# FabScan-Shield_v15.net
KiCad netlist of a schematic drawn in EAGLE
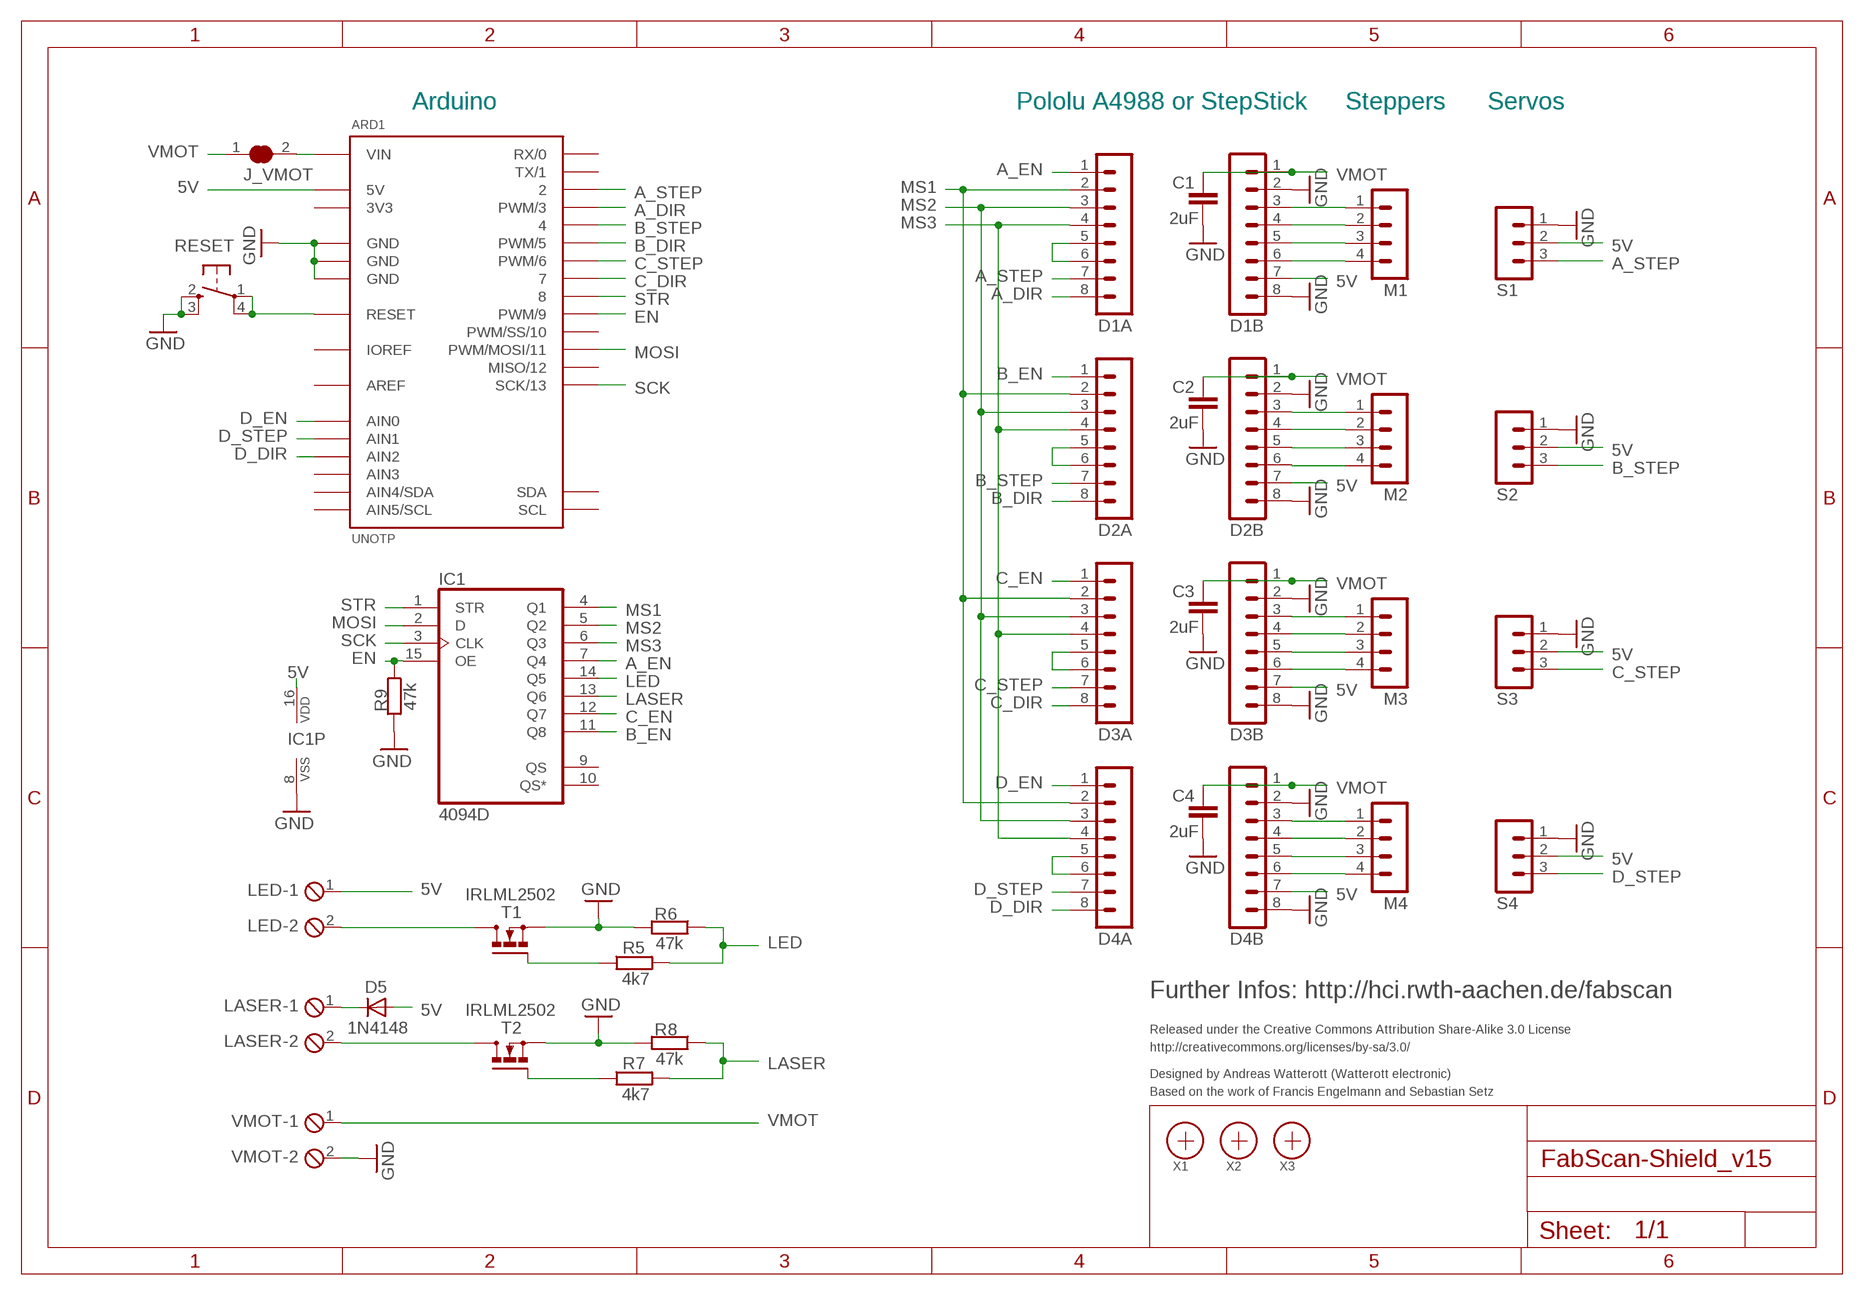
[diagram p0: schematic, sheet 1]

(export (version "E")
  (design (tool "Eeschema 10.0.6"))
  (components
    (comp (ref "ARD1")
      (value "UNOTP")
      (footprint "eagle-import:UNOTP")
      (libsource (lib "eagle-import") (part "UNOTP"))
    )
    (comp (ref "C1")
      (value "2uF")
      (footprint "eagle-import:C0603")
      (libsource (lib "eagle-import") (part "C-EUC0603"))
    )
    (comp (ref "C2")
      (value "2uF")
      (footprint "eagle-import:C0603")
      (libsource (lib "eagle-import") (part "C-EUC0603"))
    )
    (comp (ref "C3")
      (value "2uF")
      (footprint "eagle-import:C0603")
      (libsource (lib "eagle-import") (part "C-EUC0603"))
    )
    (comp (ref "C4")
      (value "2uF")
      (footprint "eagle-import:C0603")
      (libsource (lib "eagle-import") (part "C-EUC0603"))
    )
    (comp (ref "D1A")
      (value "MA08-1")
      (footprint "eagle-import:MA08-1")
      (libsource (lib "eagle-import") (part "MA08-1"))
    )
    (comp (ref "D1B")
      (value "MA08-1")
      (footprint "eagle-import:MA08-1")
      (libsource (lib "eagle-import") (part "MA08-1"))
    )
    (comp (ref "D2A")
      (value "MA08-1")
      (footprint "eagle-import:MA08-1")
      (libsource (lib "eagle-import") (part "MA08-1"))
    )
    (comp (ref "D2B")
      (value "MA08-1")
      (footprint "eagle-import:MA08-1")
      (libsource (lib "eagle-import") (part "MA08-1"))
    )
    (comp (ref "D3A")
      (value "MA08-1")
      (footprint "eagle-import:MA08-1")
      (libsource (lib "eagle-import") (part "MA08-1"))
    )
    (comp (ref "D3B")
      (value "MA08-1")
      (footprint "eagle-import:MA08-1")
      (libsource (lib "eagle-import") (part "MA08-1"))
    )
    (comp (ref "D4A")
      (value "MA08-1")
      (footprint "eagle-import:MA08-1")
      (libsource (lib "eagle-import") (part "MA08-1"))
    )
    (comp (ref "D4B")
      (value "MA08-1")
      (footprint "eagle-import:MA08-1")
      (libsource (lib "eagle-import") (part "MA08-1"))
    )
    (comp (ref "D5")
      (value "1N4148")
      (footprint "eagle-import:SOD106-R")
      (libsource (lib "eagle-import") (part "DIODE-SOD106-R"))
    )
    (comp (ref "IC1")
      (value "4094D")
      (footprint "eagle-import:SO16")
      (libsource (lib "eagle-import") (part "4094D"))
    )
    (comp (ref "J_VMOT")
      (value "SJ")
      (footprint "eagle-import:SJ")
      (libsource (lib "eagle-import") (part "SJ"))
    )
    (comp (ref "LASER")
      (value "MPT2")
      (footprint "eagle-import:2POL254")
      (fields (field (name "OC_FARNELL") "unknown") (field (name "OC_NEWARK") "unknown"))
      (libsource (lib "eagle-import") (part "MPT2"))
    )
    (comp (ref "LED")
      (value "MPT2")
      (footprint "eagle-import:2POL254")
      (libsource (lib "eagle-import") (part "MPT2"))
    )
    (comp (ref "M1")
      (value "MA04-1")
      (footprint "eagle-import:MA04-1")
      (libsource (lib "eagle-import") (part "MA04-1"))
    )
    (comp (ref "M2")
      (value "MA04-1")
      (footprint "eagle-import:MA04-1")
      (fields (field (name "OC_FARNELL") "unknown") (field (name "OC_NEWARK") "unknown"))
      (libsource (lib "eagle-import") (part "MA04-1"))
    )
    (comp (ref "M3")
      (value "MA04-1")
      (footprint "eagle-import:MA04-1")
      (fields (field (name "OC_FARNELL") "unknown") (field (name "OC_NEWARK") "unknown"))
      (libsource (lib "eagle-import") (part "MA04-1"))
    )
    (comp (ref "M4")
      (value "MA04-1")
      (footprint "eagle-import:MA04-1")
      (fields (field (name "OC_FARNELL") "unknown") (field (name "OC_NEWARK") "unknown"))
      (libsource (lib "eagle-import") (part "MA04-1"))
    )
    (comp (ref "R5")
      (value "4k7")
      (footprint "eagle-import:R0603")
      (libsource (lib "eagle-import") (part "R-EU_R0603"))
    )
    (comp (ref "R6")
      (value "47k")
      (footprint "eagle-import:R0603")
      (libsource (lib "eagle-import") (part "R-EU_R0603"))
    )
    (comp (ref "R7")
      (value "4k7")
      (footprint "eagle-import:R0603")
      (libsource (lib "eagle-import") (part "R-EU_R0603"))
    )
    (comp (ref "R8")
      (value "47k")
      (footprint "eagle-import:R0603")
      (libsource (lib "eagle-import") (part "R-EU_R0603"))
    )
    (comp (ref "R9")
      (value "47k")
      (footprint "eagle-import:R0603")
      (libsource (lib "eagle-import") (part "R-EU_R0603"))
    )
    (comp (ref "RESET")
      (value "SW_SMDS")
      (footprint "eagle-import:SW_SMD4")
      (libsource (lib "eagle-import") (part "SW_SMDS"))
    )
    (comp (ref "S1")
      (value "MA03-1")
      (footprint "eagle-import:MA03-1")
      (libsource (lib "eagle-import") (part "MA03-1"))
    )
    (comp (ref "S2")
      (value "MA03-1")
      (footprint "eagle-import:MA03-1")
      (libsource (lib "eagle-import") (part "MA03-1"))
    )
    (comp (ref "S3")
      (value "MA03-1")
      (footprint "eagle-import:MA03-1")
      (libsource (lib "eagle-import") (part "MA03-1"))
    )
    (comp (ref "S4")
      (value "MA03-1")
      (footprint "eagle-import:MA03-1")
      (libsource (lib "eagle-import") (part "MA03-1"))
    )
    (comp (ref "T1")
      (value "IRLML2502")
      (footprint "eagle-import:MICRO3")
      (libsource (lib "eagle-import") (part "IRLML2502"))
    )
    (comp (ref "T2")
      (value "IRLML2502")
      (footprint "eagle-import:MICRO3")
      (libsource (lib "eagle-import") (part "IRLML2502"))
    )
    (comp (ref "VMOT")
      (value "MPT2")
      (footprint "eagle-import:2POL254")
      (fields (field (name "OC_FARNELL") "unknown") (field (name "OC_NEWARK") "unknown"))
      (libsource (lib "eagle-import") (part "MPT2"))
    )
    (comp (ref "X1")
      (value "PASSER")
      (footprint "eagle-import:PASSER")
      (libsource (lib "eagle-import") (part "PASSER"))
    )
    (comp (ref "X2")
      (value "PASSER")
      (footprint "eagle-import:PASSER")
      (libsource (lib "eagle-import") (part "PASSER"))
    )
    (comp (ref "X3")
      (value "PASSER")
      (footprint "eagle-import:PASSER")
      (libsource (lib "eagle-import") (part "PASSER"))
    )
  )
  (nets
    (net (code "1") (name "/3V3") (class "Default")
      (node (ref "ARD1") (pin "3V3") (pinfunction "3V3_3V3") (pintype "power_in"))
    )
    (net (code "2") (name "/5V") (class "Default")
      (node (ref "ARD1") (pin "5V") (pinfunction "5V_5V") (pintype "power_in"))
      (node (ref "D1B") (pin "7") (pinfunction "7_7") (pintype "passive"))
      (node (ref "D2B") (pin "7") (pinfunction "7_7") (pintype "passive"))
      (node (ref "D3B") (pin "7") (pinfunction "7_7") (pintype "passive"))
      (node (ref "D4B") (pin "7") (pinfunction "7_7") (pintype "passive"))
      (node (ref "D5") (pin "A") (pinfunction "A_A") (pintype "passive"))
      (node (ref "IC1") (pin "16") (pinfunction "VDD_16") (pintype "power_in"))
      (node (ref "LED") (pin "1") (pinfunction "1_1") (pintype "passive"))
      (node (ref "S1") (pin "2") (pinfunction "2_2") (pintype "passive"))
      (node (ref "S2") (pin "2") (pinfunction "2_2") (pintype "passive"))
      (node (ref "S3") (pin "2") (pinfunction "2_2") (pintype "passive"))
      (node (ref "S4") (pin "2") (pinfunction "2_2") (pintype "passive"))
    )
    (net (code "3") (name "/AREF") (class "Default")
      (node (ref "ARD1") (pin "AREF") (pinfunction "AREF_AREF") (pintype "power_in"))
    )
    (net (code "4") (name "/A_DIR") (class "Default")
      (node (ref "ARD1") (pin "3") (pinfunction "PWM/3_3") (pintype "bidirectional"))
      (node (ref "D1A") (pin "8") (pinfunction "8_8") (pintype "passive"))
    )
    (net (code "5") (name "/A_EN") (class "Default")
      (node (ref "D1A") (pin "1") (pinfunction "1_1") (pintype "passive"))
      (node (ref "IC1") (pin "7") (pinfunction "Q4_7") (pintype "output"))
    )
    (net (code "6") (name "/A_STEP") (class "Default")
      (node (ref "ARD1") (pin "2") (pinfunction "2_2") (pintype "bidirectional"))
      (node (ref "D1A") (pin "7") (pinfunction "7_7") (pintype "passive"))
      (node (ref "S1") (pin "3") (pinfunction "3_3") (pintype "passive"))
    )
    (net (code "7") (name "/B_DIR") (class "Default")
      (node (ref "ARD1") (pin "5") (pinfunction "PWM/5_5") (pintype "bidirectional"))
      (node (ref "D2A") (pin "8") (pinfunction "8_8") (pintype "passive"))
    )
    (net (code "8") (name "/B_EN") (class "Default")
      (node (ref "D2A") (pin "1") (pinfunction "1_1") (pintype "passive"))
      (node (ref "IC1") (pin "11") (pinfunction "Q8_11") (pintype "output"))
    )
    (net (code "9") (name "/B_STEP") (class "Default")
      (node (ref "ARD1") (pin "4") (pinfunction "4_4") (pintype "bidirectional"))
      (node (ref "D2A") (pin "7") (pinfunction "7_7") (pintype "passive"))
      (node (ref "S2") (pin "3") (pinfunction "3_3") (pintype "passive"))
    )
    (net (code "10") (name "/C_DIR") (class "Default")
      (node (ref "ARD1") (pin "7") (pinfunction "7_7") (pintype "bidirectional"))
      (node (ref "D3A") (pin "8") (pinfunction "8_8") (pintype "passive"))
    )
    (net (code "11") (name "/C_EN") (class "Default")
      (node (ref "D3A") (pin "1") (pinfunction "1_1") (pintype "passive"))
      (node (ref "IC1") (pin "12") (pinfunction "Q7_12") (pintype "output"))
    )
    (net (code "12") (name "/C_STEP") (class "Default")
      (node (ref "ARD1") (pin "6") (pinfunction "PWM/6_6") (pintype "bidirectional"))
      (node (ref "D3A") (pin "7") (pinfunction "7_7") (pintype "passive"))
      (node (ref "S3") (pin "3") (pinfunction "3_3") (pintype "passive"))
    )
    (net (code "13") (name "/D_DIR") (class "Default")
      (node (ref "ARD1") (pin "AIN2") (pinfunction "AIN2_AIN2") (pintype "bidirectional"))
      (node (ref "D4A") (pin "8") (pinfunction "8_8") (pintype "passive"))
    )
    (net (code "14") (name "/D_EN") (class "Default")
      (node (ref "ARD1") (pin "AIN0") (pinfunction "AIN0_AIN0") (pintype "bidirectional"))
      (node (ref "D4A") (pin "1") (pinfunction "1_1") (pintype "passive"))
    )
    (net (code "15") (name "/D_STEP") (class "Default")
      (node (ref "ARD1") (pin "AIN1") (pinfunction "AIN1_AIN1") (pintype "bidirectional"))
      (node (ref "D4A") (pin "7") (pinfunction "7_7") (pintype "passive"))
      (node (ref "S4") (pin "3") (pinfunction "3_3") (pintype "passive"))
    )
    (net (code "16") (name "/EN") (class "Default")
      (node (ref "ARD1") (pin "9") (pinfunction "PWM/9_9") (pintype "bidirectional"))
      (node (ref "IC1") (pin "15") (pinfunction "OE_15") (pintype "input"))
      (node (ref "R9") (pin "1") (pinfunction "1_1") (pintype "passive"))
    )
    (net (code "17") (name "/IOREF") (class "Default")
      (node (ref "ARD1") (pin "IOREF") (pinfunction "IOREF_IOREF") (pintype "power_in"))
    )
    (net (code "18") (name "/LASER") (class "Default")
      (node (ref "IC1") (pin "13") (pinfunction "Q6_13") (pintype "output"))
      (node (ref "R7") (pin "2") (pinfunction "2_2") (pintype "passive"))
      (node (ref "R8") (pin "1") (pinfunction "1_1") (pintype "passive"))
    )
    (net (code "19") (name "/LED") (class "Default")
      (node (ref "IC1") (pin "14") (pinfunction "Q5_14") (pintype "output"))
      (node (ref "R5") (pin "2") (pinfunction "2_2") (pintype "passive"))
      (node (ref "R6") (pin "1") (pinfunction "1_1") (pintype "passive"))
    )
    (net (code "20") (name "/MOSI") (class "Default")
      (node (ref "ARD1") (pin "11") (pinfunction "PWM/MOSI/11_11") (pintype "bidirectional"))
      (node (ref "IC1") (pin "2") (pinfunction "D_2") (pintype "input"))
    )
    (net (code "21") (name "/MS1") (class "Default")
      (node (ref "D1A") (pin "2") (pinfunction "2_2") (pintype "passive"))
      (node (ref "D2A") (pin "2") (pinfunction "2_2") (pintype "passive"))
      (node (ref "D3A") (pin "2") (pinfunction "2_2") (pintype "passive"))
      (node (ref "D4A") (pin "2") (pinfunction "2_2") (pintype "passive"))
      (node (ref "IC1") (pin "4") (pinfunction "Q1_4") (pintype "output"))
    )
    (net (code "22") (name "/MS2") (class "Default")
      (node (ref "D1A") (pin "3") (pinfunction "3_3") (pintype "passive"))
      (node (ref "D2A") (pin "3") (pinfunction "3_3") (pintype "passive"))
      (node (ref "D3A") (pin "3") (pinfunction "3_3") (pintype "passive"))
      (node (ref "D4A") (pin "3") (pinfunction "3_3") (pintype "passive"))
      (node (ref "IC1") (pin "5") (pinfunction "Q2_5") (pintype "output"))
    )
    (net (code "23") (name "/MS3") (class "Default")
      (node (ref "D1A") (pin "4") (pinfunction "4_4") (pintype "passive"))
      (node (ref "D2A") (pin "4") (pinfunction "4_4") (pintype "passive"))
      (node (ref "D3A") (pin "4") (pinfunction "4_4") (pintype "passive"))
      (node (ref "D4A") (pin "4") (pinfunction "4_4") (pintype "passive"))
      (node (ref "IC1") (pin "6") (pinfunction "Q3_6") (pintype "output"))
    )
    (net (code "24") (name "/SCK") (class "Default")
      (node (ref "ARD1") (pin "13") (pinfunction "SCK/13_13") (pintype "bidirectional"))
      (node (ref "IC1") (pin "3") (pinfunction "CLK_3") (pintype "input"))
    )
    (net (code "25") (name "/STR") (class "Default")
      (node (ref "ARD1") (pin "8") (pinfunction "8_8") (pintype "bidirectional"))
      (node (ref "IC1") (pin "1") (pinfunction "STR_1") (pintype "input"))
    )
    (net (code "26") (name "/VMOT") (class "Default")
      (node (ref "C1") (pin "1") (pinfunction "1_1") (pintype "passive"))
      (node (ref "C2") (pin "1") (pinfunction "1_1") (pintype "passive"))
      (node (ref "C3") (pin "1") (pinfunction "1_1") (pintype "passive"))
      (node (ref "C4") (pin "1") (pinfunction "1_1") (pintype "passive"))
      (node (ref "D1B") (pin "1") (pinfunction "1_1") (pintype "passive"))
      (node (ref "D2B") (pin "1") (pinfunction "1_1") (pintype "passive"))
      (node (ref "D3B") (pin "1") (pinfunction "1_1") (pintype "passive"))
      (node (ref "D4B") (pin "1") (pinfunction "1_1") (pintype "passive"))
      (node (ref "J_VMOT") (pin "1") (pinfunction "1_1") (pintype "passive"))
      (node (ref "VMOT") (pin "1") (pinfunction "1_1") (pintype "passive"))
    )
    (net (code "27") (name "GND") (class "Default")
      (node (ref "ARD1") (pin "GND@1") (pinfunction "GND_GND@1") (pintype "power_in"))
      (node (ref "ARD1") (pin "GND@2") (pinfunction "GND_GND@2") (pintype "power_in"))
      (node (ref "ARD1") (pin "GND@3") (pinfunction "GND_GND@3") (pintype "power_in"))
      (node (ref "C1") (pin "2") (pinfunction "2_2") (pintype "passive"))
      (node (ref "C2") (pin "2") (pinfunction "2_2") (pintype "passive"))
      (node (ref "C3") (pin "2") (pinfunction "2_2") (pintype "passive"))
      (node (ref "C4") (pin "2") (pinfunction "2_2") (pintype "passive"))
      (node (ref "D1B") (pin "2") (pinfunction "2_2") (pintype "passive"))
      (node (ref "D1B") (pin "8") (pinfunction "8_8") (pintype "passive"))
      (node (ref "D2B") (pin "2") (pinfunction "2_2") (pintype "passive"))
      (node (ref "D2B") (pin "8") (pinfunction "8_8") (pintype "passive"))
      (node (ref "D3B") (pin "2") (pinfunction "2_2") (pintype "passive"))
      (node (ref "D3B") (pin "8") (pinfunction "8_8") (pintype "passive"))
      (node (ref "D4B") (pin "2") (pinfunction "2_2") (pintype "passive"))
      (node (ref "D4B") (pin "8") (pinfunction "8_8") (pintype "passive"))
      (node (ref "IC1") (pin "8") (pinfunction "VSS_8") (pintype "power_in"))
      (node (ref "R6") (pin "2") (pinfunction "2_2") (pintype "passive"))
      (node (ref "R8") (pin "2") (pinfunction "2_2") (pintype "passive"))
      (node (ref "R9") (pin "2") (pinfunction "2_2") (pintype "passive"))
      (node (ref "RESET") (pin "2") (pinfunction "S_2") (pintype "passive"))
      (node (ref "RESET") (pin "3") (pinfunction "S1_3") (pintype "passive"))
      (node (ref "S1") (pin "1") (pinfunction "1_1") (pintype "passive"))
      (node (ref "S2") (pin "1") (pinfunction "1_1") (pintype "passive"))
      (node (ref "S3") (pin "1") (pinfunction "1_1") (pintype "passive"))
      (node (ref "S4") (pin "1") (pinfunction "1_1") (pintype "passive"))
      (node (ref "T1") (pin "2") (pinfunction "S_2") (pintype "passive"))
      (node (ref "T2") (pin "2") (pinfunction "S_2") (pintype "passive"))
      (node (ref "VMOT") (pin "2") (pinfunction "1_2") (pintype "passive"))
    )
    (net (code "28") (name "Net-(ARD1-PadVIN)") (class "Default")
      (node (ref "ARD1") (pin "VIN") (pinfunction "VIN_VIN") (pintype "power_in"))
      (node (ref "J_VMOT") (pin "2") (pinfunction "2_2") (pintype "passive"))
    )
    (net (code "29") (name "Net-(ARD1-RESET)") (class "Default")
      (node (ref "ARD1") (pin "RST") (pinfunction "RESET_RST") (pintype "bidirectional"))
      (node (ref "RESET") (pin "1") (pinfunction "P_1") (pintype "passive"))
      (node (ref "RESET") (pin "4") (pinfunction "P1_4") (pintype "passive"))
    )
    (net (code "30") (name "Net-(D1A-Pad5)") (class "Default")
      (node (ref "D1A") (pin "5") (pinfunction "5_5") (pintype "passive"))
      (node (ref "D1A") (pin "6") (pinfunction "6_6") (pintype "passive"))
    )
    (net (code "31") (name "Net-(D1B-Pad3)") (class "Default")
      (node (ref "D1B") (pin "3") (pinfunction "3_3") (pintype "passive"))
      (node (ref "M1") (pin "1") (pinfunction "1_1") (pintype "passive"))
    )
    (net (code "32") (name "Net-(D1B-Pad4)") (class "Default")
      (node (ref "D1B") (pin "4") (pinfunction "4_4") (pintype "passive"))
      (node (ref "M1") (pin "2") (pinfunction "2_2") (pintype "passive"))
    )
    (net (code "33") (name "Net-(D1B-Pad5)") (class "Default")
      (node (ref "D1B") (pin "5") (pinfunction "5_5") (pintype "passive"))
      (node (ref "M1") (pin "3") (pinfunction "3_3") (pintype "passive"))
    )
    (net (code "34") (name "Net-(D1B-Pad6)") (class "Default")
      (node (ref "D1B") (pin "6") (pinfunction "6_6") (pintype "passive"))
      (node (ref "M1") (pin "4") (pinfunction "4_4") (pintype "passive"))
    )
    (net (code "35") (name "Net-(D2A-Pad5)") (class "Default")
      (node (ref "D2A") (pin "5") (pinfunction "5_5") (pintype "passive"))
      (node (ref "D2A") (pin "6") (pinfunction "6_6") (pintype "passive"))
    )
    (net (code "36") (name "Net-(D2B-Pad3)") (class "Default")
      (node (ref "D2B") (pin "3") (pinfunction "3_3") (pintype "passive"))
      (node (ref "M2") (pin "1") (pinfunction "1_1") (pintype "passive"))
    )
    (net (code "37") (name "Net-(D2B-Pad4)") (class "Default")
      (node (ref "D2B") (pin "4") (pinfunction "4_4") (pintype "passive"))
      (node (ref "M2") (pin "2") (pinfunction "2_2") (pintype "passive"))
    )
    (net (code "38") (name "Net-(D2B-Pad5)") (class "Default")
      (node (ref "D2B") (pin "5") (pinfunction "5_5") (pintype "passive"))
      (node (ref "M2") (pin "3") (pinfunction "3_3") (pintype "passive"))
    )
    (net (code "39") (name "Net-(D2B-Pad6)") (class "Default")
      (node (ref "D2B") (pin "6") (pinfunction "6_6") (pintype "passive"))
      (node (ref "M2") (pin "4") (pinfunction "4_4") (pintype "passive"))
    )
    (net (code "40") (name "Net-(D3A-Pad5)") (class "Default")
      (node (ref "D3A") (pin "5") (pinfunction "5_5") (pintype "passive"))
      (node (ref "D3A") (pin "6") (pinfunction "6_6") (pintype "passive"))
    )
    (net (code "41") (name "Net-(D3B-Pad3)") (class "Default")
      (node (ref "D3B") (pin "3") (pinfunction "3_3") (pintype "passive"))
      (node (ref "M3") (pin "1") (pinfunction "1_1") (pintype "passive"))
    )
    (net (code "42") (name "Net-(D3B-Pad4)") (class "Default")
      (node (ref "D3B") (pin "4") (pinfunction "4_4") (pintype "passive"))
      (node (ref "M3") (pin "2") (pinfunction "2_2") (pintype "passive"))
    )
    (net (code "43") (name "Net-(D3B-Pad5)") (class "Default")
      (node (ref "D3B") (pin "5") (pinfunction "5_5") (pintype "passive"))
      (node (ref "M3") (pin "3") (pinfunction "3_3") (pintype "passive"))
    )
    (net (code "44") (name "Net-(D3B-Pad6)") (class "Default")
      (node (ref "D3B") (pin "6") (pinfunction "6_6") (pintype "passive"))
      (node (ref "M3") (pin "4") (pinfunction "4_4") (pintype "passive"))
    )
    (net (code "45") (name "Net-(D4A-Pad5)") (class "Default")
      (node (ref "D4A") (pin "5") (pinfunction "5_5") (pintype "passive"))
      (node (ref "D4A") (pin "6") (pinfunction "6_6") (pintype "passive"))
    )
    (net (code "46") (name "Net-(D4B-Pad3)") (class "Default")
      (node (ref "D4B") (pin "3") (pinfunction "3_3") (pintype "passive"))
      (node (ref "M4") (pin "1") (pinfunction "1_1") (pintype "passive"))
    )
    (net (code "47") (name "Net-(D4B-Pad4)") (class "Default")
      (node (ref "D4B") (pin "4") (pinfunction "4_4") (pintype "passive"))
      (node (ref "M4") (pin "2") (pinfunction "2_2") (pintype "passive"))
    )
    (net (code "48") (name "Net-(D4B-Pad5)") (class "Default")
      (node (ref "D4B") (pin "5") (pinfunction "5_5") (pintype "passive"))
      (node (ref "M4") (pin "3") (pinfunction "3_3") (pintype "passive"))
    )
    (net (code "49") (name "Net-(D4B-Pad6)") (class "Default")
      (node (ref "D4B") (pin "6") (pinfunction "6_6") (pintype "passive"))
      (node (ref "M4") (pin "4") (pinfunction "4_4") (pintype "passive"))
    )
    (net (code "50") (name "Net-(D5-PadC)") (class "Default")
      (node (ref "D5") (pin "C") (pinfunction "C_C") (pintype "passive"))
      (node (ref "LASER") (pin "1") (pinfunction "1_1") (pintype "passive"))
    )
    (net (code "51") (name "Net-(LASERB-1)") (class "Default")
      (node (ref "LASER") (pin "2") (pinfunction "1_2") (pintype "passive"))
      (node (ref "T2") (pin "3") (pinfunction "D_3") (pintype "passive"))
    )
    (net (code "52") (name "Net-(LEDB-1)") (class "Default")
      (node (ref "LED") (pin "2") (pinfunction "1_2") (pintype "passive"))
      (node (ref "T1") (pin "3") (pinfunction "D_3") (pintype "passive"))
    )
    (net (code "53") (name "Net-(T1-G)") (class "Default")
      (node (ref "R5") (pin "1") (pinfunction "1_1") (pintype "passive"))
      (node (ref "T1") (pin "1") (pinfunction "G_1") (pintype "passive"))
    )
    (net (code "54") (name "Net-(T2-G)") (class "Default")
      (node (ref "R7") (pin "1") (pinfunction "1_1") (pintype "passive"))
      (node (ref "T2") (pin "1") (pinfunction "G_1") (pintype "passive"))
    )
    (net (code "55") (name "unconnected-(ARD1-AIN4{slash}SDA-PadAIN4)") (class "Default")
      (node (ref "ARD1") (pin "AIN4") (pinfunction "AIN4/SDA_AIN4") (pintype "bidirectional"))
    )
    (net (code "56") (name "unconnected-(ARD1-AIN5{slash}SCL-PadAIN5)") (class "Default")
      (node (ref "ARD1") (pin "AIN5") (pinfunction "AIN5/SCL_AIN5") (pintype "bidirectional"))
    )
    (net (code "57") (name "unconnected-(ARD1-MISO{slash}12-Pad12)") (class "Default")
      (node (ref "ARD1") (pin "12") (pinfunction "MISO/12_12") (pintype "bidirectional"))
    )
    (net (code "58") (name "unconnected-(ARD1-PWM{slash}SS{slash}10-Pad10)") (class "Default")
      (node (ref "ARD1") (pin "10") (pinfunction "PWM/SS/10_10") (pintype "bidirectional"))
    )
    (net (code "59") (name "unconnected-(ARD1-PadAIN3)") (class "Default")
      (node (ref "ARD1") (pin "AIN3") (pinfunction "AIN3_AIN3") (pintype "bidirectional"))
    )
    (net (code "60") (name "unconnected-(ARD1-PadSCL)") (class "Default")
      (node (ref "ARD1") (pin "SCL") (pinfunction "SCL_SCL") (pintype "bidirectional"))
    )
    (net (code "61") (name "unconnected-(ARD1-PadSDA)") (class "Default")
      (node (ref "ARD1") (pin "SDA") (pinfunction "SDA_SDA") (pintype "bidirectional"))
    )
    (net (code "62") (name "unconnected-(ARD1-RX{slash}0-Pad0)") (class "Default")
      (node (ref "ARD1") (pin "0") (pinfunction "RX/0_0") (pintype "bidirectional"))
    )
    (net (code "63") (name "unconnected-(ARD1-TX{slash}1-Pad1)") (class "Default")
      (node (ref "ARD1") (pin "1") (pinfunction "TX/1_1") (pintype "bidirectional"))
    )
    (net (code "64") (name "unconnected-(IC1A-QS*-Pad10)") (class "Default")
      (node (ref "IC1") (pin "10") (pinfunction "QS*_10") (pintype "output"))
    )
    (net (code "65") (name "unconnected-(IC1A-QS-Pad9)") (class "Default")
      (node (ref "IC1") (pin "9") (pinfunction "QS_9") (pintype "output"))
    )
  )
)
